# Ideal_Diode.net
KiCad netlist of a schematic drawn in Altium Designer
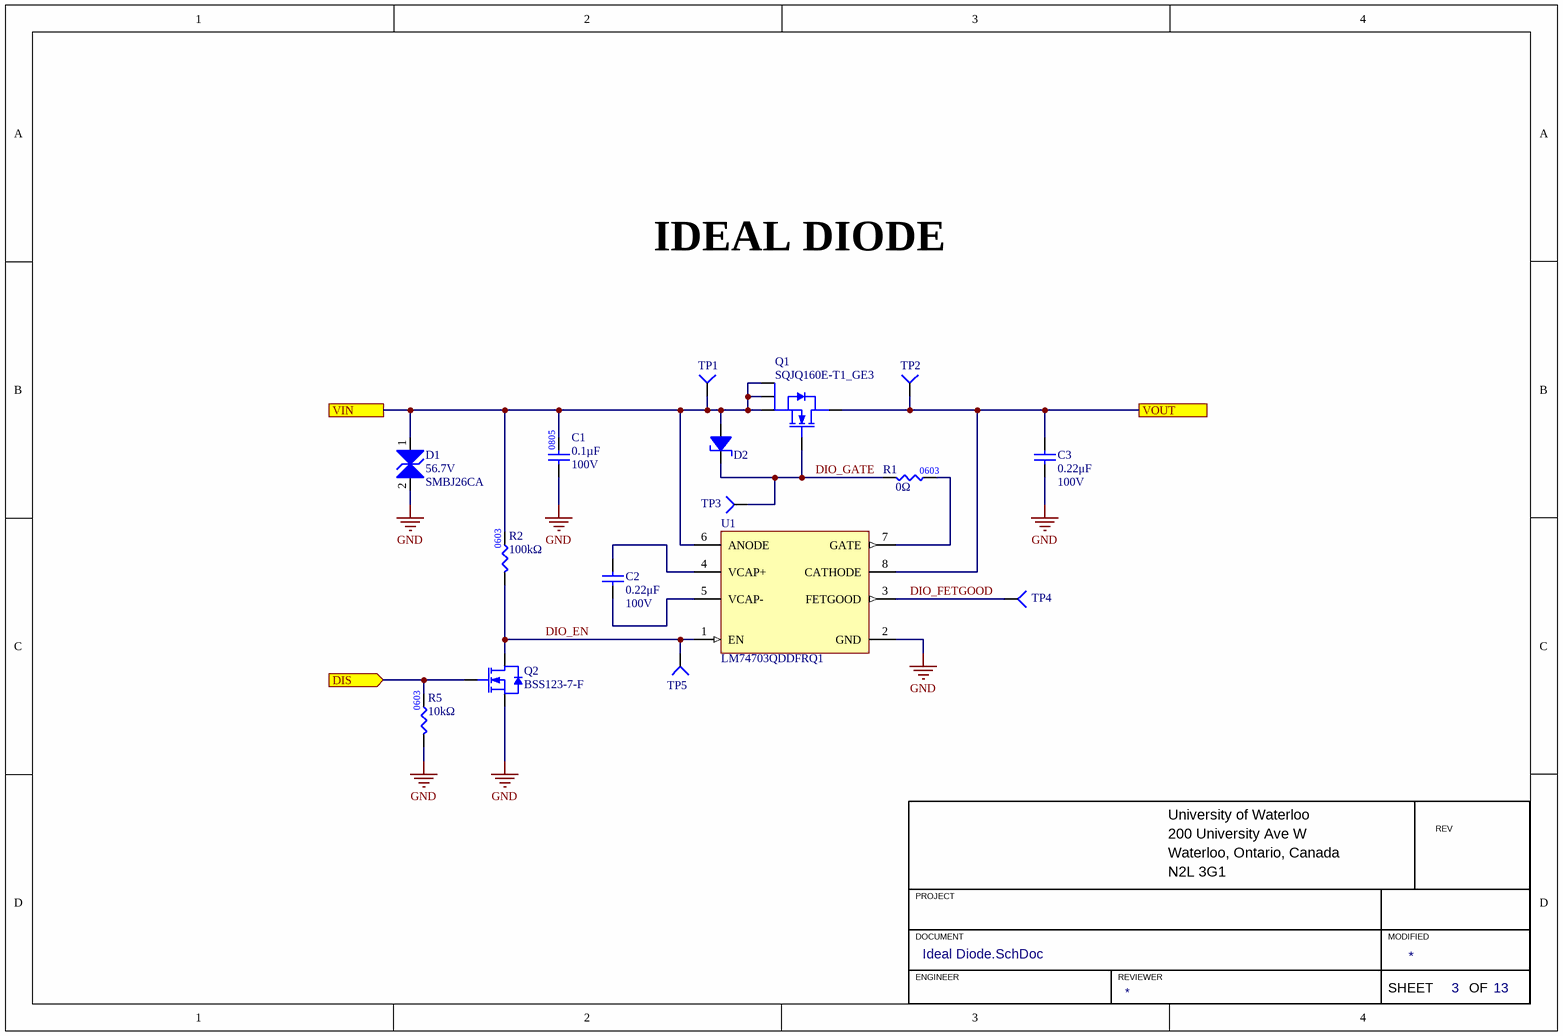
[diagram p0: Ideal Diode.SchDoc]

(export (version "E")
  (design (tool "Eeschema 10.0.6"))
  (components
    (comp (ref "C1")
      (value "0.1µF")
      (footprint "CAP0805")
      (description "CAP CER 0.1UF 100V X7R 0805")
      (fields (field (name "VOLTAGE RATING") "100V") (field (name "Comment") "CAP_0.1uF_100V_0805"))
      (libsource (lib "Personal_Schematic_Library_2022") (part "CAP_0.1uF_100V_0805"))
    )
    (comp (ref "C2")
      (value "0.22μF")
      (footprint "CAP0805")
      (description "CAP CER 0.22UF 100V X7R 0805")
      (fields (field (name "VOLTAGE RATING") "100V") (field (name "Comment") "CAP_0.22uF_100V_0805"))
      (libsource (lib "Personal_Schematic_Library_2022") (part "CAP_0.22uF_100V_0805"))
    )
    (comp (ref "C3")
      (value "0.22μF")
      (footprint "CAP0805")
      (description "CAP CER 0.22UF 100V X7R 0805")
      (fields (field (name "VOLTAGE RATING") "100V") (field (name "Comment") "CAP_0.22uF_100V_0805"))
      (libsource (lib "Personal_Schematic_Library_2022") (part "CAP_0.22uF_100V_0805"))
    )
    (comp (ref "D1")
      (value "TVS_DIODE_BIDIR_51V")
      (footprint "TVS_DIODE_BIDIR_SMB")
      (description "TVS DIODE 51VWM 82.4VC DO214AA")
      (fields
        (field (name "VOLTAGE - BREAKDOWN (MIN)") "56.7V")
        (field (name "MANUFACTURER PART NUMBER 1") "SMBJ26CA")
      )
      (libsource (lib "Personal_Schematic_Library_2022") (part "TVS_DIODE_BIDIR_51V"))
    )
    (comp (ref "D2")
      (value "DIO_ZENER_16V")
      (footprint "SOD-123_FLAT")
      (description "DIODE ZENER 16V 500MW SOD123")
      (libsource (lib "Personal_Schematic_Library_2022") (part "DIO_ZENER_16V"))
    )
    (comp (ref "Q1")
      (value "NMOS_60V_603A")
      (footprint "VISHAY_PowerPAK-8x8")
      (description "AUTOMOTIVE N-CHANNEL 60 V (D-S)")
      (fields (field (name "MANUFACTURER PART NUMBER 1") "SQJQ160E-T1_GE3"))
      (libsource (lib "Personal_Schematic_Library_2022") (part "NMOS_60V_603A"))
    )
    (comp (ref "Q2")
      (value "NMOS_100V_170mA")
      (footprint "SOT23-3")
      (description "MOSFET N-CH 100V 170MA SOT23-3")
      (fields (field (name "MANUFACTURER PART NUMBER 1") "BSS123-7-F"))
      (libsource (lib "Personal_Schematic_Library_2022") (part "NMOS_100V_170mA"))
    )
    (comp (ref "R1")
      (value "0Ω")
      (footprint "RES0603")
      (description "RES 0 OHM JUMPER 1/10W 0603")
      (fields (field (name "Comment") "RES_0Ω_0603"))
      (libsource (lib "Personal_Schematic_Library_2022") (part "RES_0Ω_0603"))
    )
    (comp (ref "R2")
      (value "100kΩ")
      (footprint "RES0603")
      (description "RES 100K OHM 1% 1/10W 0603")
      (fields (field (name "Comment") "RES_100kΩ_0603_1%"))
      (libsource (lib "Personal_Schematic_Library_2022") (part "RES_100kΩ_0603_1%"))
    )
    (comp (ref "R5")
      (value "10kΩ")
      (footprint "RES0603")
      (description "RES 10K OHM 1% 1/8W 0603")
      (fields (field (name "Comment") "RES_10kΩ_0603_1%"))
      (libsource (lib "Personal_Schematic_Library_2022") (part "RES_10kΩ_0603_1%"))
    )
    (comp (ref "TP1")
      (value "TESTPOINT_1MM_SQUARE")
      (footprint "TESTPOINT_SQUARE_1MM")
      (description "TESTPOINT 1MM SQUARE")
      (libsource (lib "Personal_Schematic_Library_2022") (part "TESTPOINT_1MM_SQUARE"))
    )
    (comp (ref "TP2")
      (value "TESTPOINT_1MM_SQUARE")
      (footprint "TESTPOINT_SQUARE_1MM")
      (description "TESTPOINT 1MM SQUARE")
      (libsource (lib "Personal_Schematic_Library_2022") (part "TESTPOINT_1MM_SQUARE"))
    )
    (comp (ref "TP3")
      (value "TESTPOINT_1MM_CIRCLE")
      (footprint "TESTPOINT_CIRCLE_1MM")
      (description "TESTPOINT 1MM CIRCLE")
      (libsource (lib "Personal_Schematic_Library_2022") (part "TESTPOINT_1MM_CIRCLE"))
    )
    (comp (ref "TP4")
      (value "TESTPOINT_1MM_CIRCLE")
      (footprint "TESTPOINT_CIRCLE_1MM")
      (description "TESTPOINT 1MM CIRCLE")
      (libsource (lib "Personal_Schematic_Library_2022") (part "TESTPOINT_1MM_CIRCLE"))
    )
    (comp (ref "TP5")
      (value "TESTPOINT_1MM_CIRCLE")
      (footprint "TESTPOINT_CIRCLE_1MM")
      (description "TESTPOINT 1MM CIRCLE")
      (libsource (lib "Personal_Schematic_Library_2022") (part "TESTPOINT_1MM_CIRCLE"))
    )
    (comp (ref "U1")
      (value "LM74703QDDFRQ1")
      (footprint "TI_SOT23-8")
      (description "AUTOMOTIVE IDEAL DIODE CONTROLLE")
      (libsource (lib "Personal_Schematic_Library_2022") (part "LM74703QDDFRQ1"))
    )
  )
  (nets
    (net (code "1") (name "/DIO_EN") (class "Default")
      (node (ref "Q2") (pin "3") (pinfunction "DRAIN_3") (pintype "passive"))
      (node (ref "R2") (pin "1") (pinfunction "1_1") (pintype "passive"))
      (node (ref "TP5") (pin "1") (pinfunction "=value_1") (pintype "passive"))
      (node (ref "U1") (pin "1") (pinfunction "EN_1") (pintype "input"))
    )
    (net (code "2") (name "/DIO_FETGOOD") (class "Default")
      (node (ref "TP4") (pin "1") (pinfunction "=value_1") (pintype "passive"))
      (node (ref "U1") (pin "3") (pinfunction "FETGOOD_3") (pintype "output"))
    )
    (net (code "3") (name "/DIO_GATE") (class "Default")
      (node (ref "D2") (pin "2") (pinfunction "Cathode_2") (pintype "passive"))
      (node (ref "Q1") (pin "1") (pinfunction "Gate_1") (pintype "passive"))
      (node (ref "R1") (pin "1") (pinfunction "1_1") (pintype "passive"))
      (node (ref "TP3") (pin "1") (pinfunction "=value_1") (pintype "passive"))
    )
    (net (code "4") (name "/DIS") (class "Default")
      (node (ref "Q2") (pin "1") (pinfunction "GATE_1") (pintype "passive"))
      (node (ref "R5") (pin "2") (pinfunction "2_2") (pintype "passive"))
    )
    (net (code "5") (name "/VIN") (class "Default")
      (node (ref "C1") (pin "2") (pinfunction "2_2") (pintype "passive"))
      (node (ref "D1") (pin "1") (pinfunction "1_1") (pintype "passive"))
      (node (ref "D2") (pin "1") (pinfunction "Anode_1") (pintype "passive"))
      (node (ref "Q1") (pin "2") (pinfunction "Source_2") (pintype "passive"))
      (node (ref "Q1") (pin "3") (pinfunction "Source_3") (pintype "passive"))
      (node (ref "Q1") (pin "4") (pinfunction "Source_4") (pintype "passive"))
      (node (ref "R2") (pin "2") (pinfunction "2_2") (pintype "passive"))
      (node (ref "TP1") (pin "1") (pinfunction "=value_1") (pintype "passive"))
      (node (ref "U1") (pin "6") (pinfunction "ANODE_6") (pintype "power_in"))
    )
    (net (code "6") (name "/VOUT") (class "Default")
      (node (ref "C3") (pin "2") (pinfunction "2_2") (pintype "passive"))
      (node (ref "Q1") (pin "5") (pinfunction "Drain_5") (pintype "passive"))
      (node (ref "TP2") (pin "1") (pinfunction "=value_1") (pintype "passive"))
      (node (ref "U1") (pin "8") (pinfunction "CATHODE_8") (pintype "power_in"))
    )
    (net (code "7") (name "GND") (class "Default")
      (node (ref "C1") (pin "1") (pinfunction "1_1") (pintype "passive"))
      (node (ref "C3") (pin "1") (pinfunction "1_1") (pintype "passive"))
      (node (ref "D1") (pin "2") (pinfunction "2_2") (pintype "passive"))
      (node (ref "Q2") (pin "2") (pinfunction "SOURCE_2") (pintype "passive"))
      (node (ref "R5") (pin "1") (pinfunction "1_1") (pintype "passive"))
      (node (ref "U1") (pin "2") (pinfunction "GND_2") (pintype "power_in"))
    )
    (net (code "8") (name "Net-(U1-GATE)") (class "Default")
      (node (ref "R1") (pin "2") (pinfunction "2_2") (pintype "passive"))
      (node (ref "U1") (pin "7") (pinfunction "GATE_7") (pintype "output"))
    )
    (net (code "9") (name "Net-(U1-VCAP+)") (class "Default")
      (node (ref "C2") (pin "2") (pinfunction "2_2") (pintype "passive"))
      (node (ref "U1") (pin "4") (pinfunction "VCAP+_4") (pintype "power_in"))
    )
    (net (code "10") (name "Net-(U1-VCAP-)") (class "Default")
      (node (ref "C2") (pin "1") (pinfunction "1_1") (pintype "passive"))
      (node (ref "U1") (pin "5") (pinfunction "VCAP-_5") (pintype "power_in"))
    )
  )
)
